# open2014.net
KiCad netlist of a schematic drawn in EAGLE
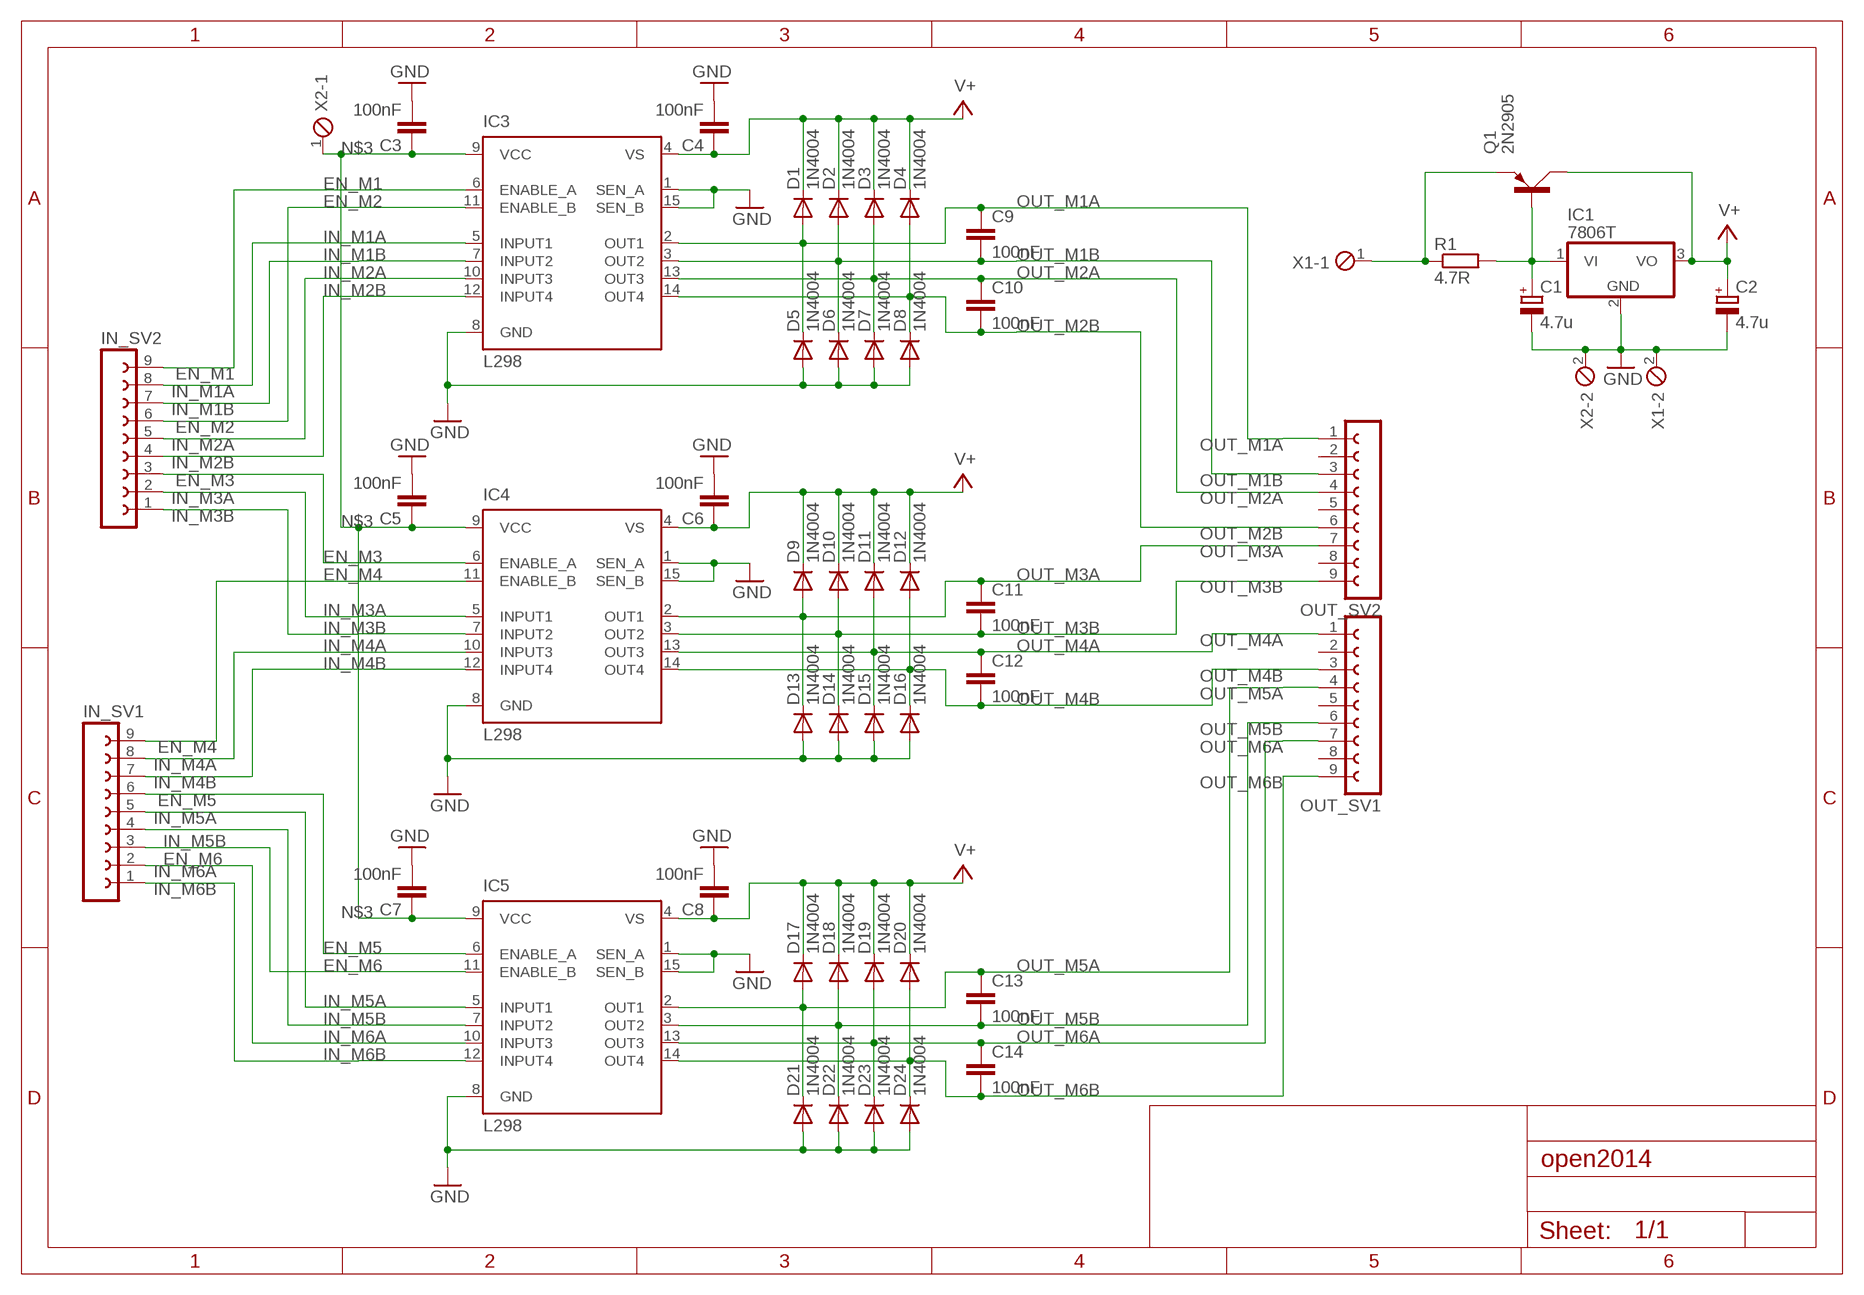
[diagram p0: schematic, sheet 1]

(export (version "E")
  (design (tool "Eeschema 10.0.6"))
  (components
    (comp (ref "C1")
      (value "4.7u")
      (footprint "eagle-import:E2,5-6")
      (libsource (lib "eagle-import") (part "CPOL-EUE2.5-6"))
    )
    (comp (ref "C2")
      (value "4.7u")
      (footprint "eagle-import:E2,5-6")
      (libsource (lib "eagle-import") (part "CPOL-EUE2.5-6"))
    )
    (comp (ref "C3")
      (value "100nF")
      (footprint "eagle-import:C050-050X075")
      (libsource (lib "eagle-import") (part "C-EU050-050X075"))
    )
    (comp (ref "C4")
      (value "100nF")
      (footprint "eagle-import:C050-050X075")
      (libsource (lib "eagle-import") (part "C-EU050-050X075"))
    )
    (comp (ref "C5")
      (value "100nF")
      (footprint "eagle-import:C050-050X075")
      (libsource (lib "eagle-import") (part "C-EU050-050X075"))
    )
    (comp (ref "C6")
      (value "100nF")
      (footprint "eagle-import:C050-050X075")
      (libsource (lib "eagle-import") (part "C-EU050-050X075"))
    )
    (comp (ref "C7")
      (value "100nF")
      (footprint "eagle-import:C050-050X075")
      (libsource (lib "eagle-import") (part "C-EU050-050X075"))
    )
    (comp (ref "C8")
      (value "100nF")
      (footprint "eagle-import:C050-050X075")
      (libsource (lib "eagle-import") (part "C-EU050-050X075"))
    )
    (comp (ref "C9")
      (value "100nF")
      (footprint "eagle-import:C050-050X075")
      (libsource (lib "eagle-import") (part "C-EU050-050X075"))
    )
    (comp (ref "C10")
      (value "100nF")
      (footprint "eagle-import:C050-050X075")
      (libsource (lib "eagle-import") (part "C-EU050-050X075"))
    )
    (comp (ref "C11")
      (value "100nF")
      (footprint "eagle-import:C050-050X075")
      (libsource (lib "eagle-import") (part "C-EU050-050X075"))
    )
    (comp (ref "C12")
      (value "100nF")
      (footprint "eagle-import:C050-050X075")
      (libsource (lib "eagle-import") (part "C-EU050-050X075"))
    )
    (comp (ref "C13")
      (value "100nF")
      (footprint "eagle-import:C050-050X075")
      (libsource (lib "eagle-import") (part "C-EU050-050X075"))
    )
    (comp (ref "C14")
      (value "100nF")
      (footprint "eagle-import:C050-050X075")
      (libsource (lib "eagle-import") (part "C-EU050-050X075"))
    )
    (comp (ref "D1")
      (value "1N4004")
      (footprint "eagle-import:DO41-10")
      (libsource (lib "eagle-import") (part "1N4004"))
    )
    (comp (ref "D2")
      (value "1N4004")
      (footprint "eagle-import:DO41-10")
      (libsource (lib "eagle-import") (part "1N4004"))
    )
    (comp (ref "D3")
      (value "1N4004")
      (footprint "eagle-import:DO41-10")
      (libsource (lib "eagle-import") (part "1N4004"))
    )
    (comp (ref "D4")
      (value "1N4004")
      (footprint "eagle-import:DO41-10")
      (libsource (lib "eagle-import") (part "1N4004"))
    )
    (comp (ref "D5")
      (value "1N4004")
      (footprint "eagle-import:DO41-10")
      (libsource (lib "eagle-import") (part "1N4004"))
    )
    (comp (ref "D6")
      (value "1N4004")
      (footprint "eagle-import:DO41-10")
      (libsource (lib "eagle-import") (part "1N4004"))
    )
    (comp (ref "D7")
      (value "1N4004")
      (footprint "eagle-import:DO41-10")
      (libsource (lib "eagle-import") (part "1N4004"))
    )
    (comp (ref "D8")
      (value "1N4004")
      (footprint "eagle-import:DO41-10")
      (libsource (lib "eagle-import") (part "1N4004"))
    )
    (comp (ref "D9")
      (value "1N4004")
      (footprint "eagle-import:DO41-10")
      (libsource (lib "eagle-import") (part "1N4004"))
    )
    (comp (ref "D10")
      (value "1N4004")
      (footprint "eagle-import:DO41-10")
      (libsource (lib "eagle-import") (part "1N4004"))
    )
    (comp (ref "D11")
      (value "1N4004")
      (footprint "eagle-import:DO41-10")
      (libsource (lib "eagle-import") (part "1N4004"))
    )
    (comp (ref "D12")
      (value "1N4004")
      (footprint "eagle-import:DO41-10")
      (libsource (lib "eagle-import") (part "1N4004"))
    )
    (comp (ref "D13")
      (value "1N4004")
      (footprint "eagle-import:DO41-10")
      (libsource (lib "eagle-import") (part "1N4004"))
    )
    (comp (ref "D14")
      (value "1N4004")
      (footprint "eagle-import:DO41-10")
      (libsource (lib "eagle-import") (part "1N4004"))
    )
    (comp (ref "D15")
      (value "1N4004")
      (footprint "eagle-import:DO41-10")
      (libsource (lib "eagle-import") (part "1N4004"))
    )
    (comp (ref "D16")
      (value "1N4004")
      (footprint "eagle-import:DO41-10")
      (libsource (lib "eagle-import") (part "1N4004"))
    )
    (comp (ref "D17")
      (value "1N4004")
      (footprint "eagle-import:DO41-10")
      (libsource (lib "eagle-import") (part "1N4004"))
    )
    (comp (ref "D18")
      (value "1N4004")
      (footprint "eagle-import:DO41-10")
      (libsource (lib "eagle-import") (part "1N4004"))
    )
    (comp (ref "D19")
      (value "1N4004")
      (footprint "eagle-import:DO41-10")
      (libsource (lib "eagle-import") (part "1N4004"))
    )
    (comp (ref "D20")
      (value "1N4004")
      (footprint "eagle-import:DO41-10")
      (libsource (lib "eagle-import") (part "1N4004"))
    )
    (comp (ref "D21")
      (value "1N4004")
      (footprint "eagle-import:DO41-10")
      (libsource (lib "eagle-import") (part "1N4004"))
    )
    (comp (ref "D22")
      (value "1N4004")
      (footprint "eagle-import:DO41-10")
      (libsource (lib "eagle-import") (part "1N4004"))
    )
    (comp (ref "D23")
      (value "1N4004")
      (footprint "eagle-import:DO41-10")
      (libsource (lib "eagle-import") (part "1N4004"))
    )
    (comp (ref "D24")
      (value "1N4004")
      (footprint "eagle-import:DO41-10")
      (libsource (lib "eagle-import") (part "1N4004"))
    )
    (comp (ref "IC1")
      (value "7806T")
      (footprint "eagle-import:TO220H")
      (libsource (lib "eagle-import") (part "78T06"))
    )
    (comp (ref "IC3")
      (value "L298")
      (footprint "eagle-import:MULTIWATT-15")
      (fields (field (name "MPN") "L298N"))
      (libsource (lib "eagle-import") (part "L298"))
    )
    (comp (ref "IC4")
      (value "L298")
      (footprint "eagle-import:MULTIWATT-15")
      (fields (field (name "MPN") "L298N"))
      (libsource (lib "eagle-import") (part "L298"))
    )
    (comp (ref "IC5")
      (value "L298")
      (footprint "eagle-import:MULTIWATT-15")
      (fields (field (name "MPN") "L298N"))
      (libsource (lib "eagle-import") (part "L298"))
    )
    (comp (ref "IN_SV1")
      (value "FE09-1")
      (footprint "eagle-import:FE09")
      (libsource (lib "eagle-import") (part "FE09-1"))
    )
    (comp (ref "IN_SV2")
      (value "FE09-1")
      (footprint "eagle-import:FE09")
      (libsource (lib "eagle-import") (part "FE09-1"))
    )
    (comp (ref "OUT_SV1")
      (value "FE09-1")
      (footprint "eagle-import:FE09")
      (libsource (lib "eagle-import") (part "FE09-1"))
    )
    (comp (ref "OUT_SV2")
      (value "FE09-1")
      (footprint "eagle-import:FE09")
      (libsource (lib "eagle-import") (part "FE09-1"))
    )
    (comp (ref "Q1")
      (value "2N2905")
      (footprint "eagle-import:TO39")
      (libsource (lib "eagle-import") (part "2N2905"))
    )
    (comp (ref "R1")
      (value "4.7R")
      (footprint "eagle-import:0411_15")
      (libsource (lib "eagle-import") (part "R-EU_0411/15"))
    )
    (comp (ref "X1")
      (value "MPT2")
      (footprint "eagle-import:2POL254")
      (libsource (lib "eagle-import") (part "MPT2"))
    )
    (comp (ref "X2")
      (value "MPT2")
      (footprint "eagle-import:2POL254")
      (libsource (lib "eagle-import") (part "MPT2"))
    )
  )
  (nets
    (net (code "1") (name "/EN_M1") (class "Default")
      (node (ref "IC3") (pin "6") (pinfunction "ENABLE_A_6") (pintype "input"))
      (node (ref "IN_SV2") (pin "9") (pinfunction "9_9") (pintype "passive"))
    )
    (net (code "2") (name "/EN_M2") (class "Default")
      (node (ref "IC3") (pin "11") (pinfunction "ENABLE_B_11") (pintype "input"))
      (node (ref "IN_SV2") (pin "6") (pinfunction "6_6") (pintype "passive"))
    )
    (net (code "3") (name "/EN_M3") (class "Default")
      (node (ref "IC4") (pin "6") (pinfunction "ENABLE_A_6") (pintype "input"))
      (node (ref "IN_SV2") (pin "3") (pinfunction "3_3") (pintype "passive"))
    )
    (net (code "4") (name "/EN_M4") (class "Default")
      (node (ref "IC4") (pin "11") (pinfunction "ENABLE_B_11") (pintype "input"))
      (node (ref "IN_SV1") (pin "9") (pinfunction "9_9") (pintype "passive"))
    )
    (net (code "5") (name "/EN_M5") (class "Default")
      (node (ref "IC5") (pin "6") (pinfunction "ENABLE_A_6") (pintype "input"))
      (node (ref "IN_SV1") (pin "6") (pinfunction "6_6") (pintype "passive"))
    )
    (net (code "6") (name "/EN_M6") (class "Default")
      (node (ref "IC5") (pin "11") (pinfunction "ENABLE_B_11") (pintype "input"))
      (node (ref "IN_SV1") (pin "3") (pinfunction "3_3") (pintype "passive"))
    )
    (net (code "7") (name "/IN_M1A") (class "Default")
      (node (ref "IC3") (pin "5") (pinfunction "INPUT1_5") (pintype "input"))
      (node (ref "IN_SV2") (pin "8") (pinfunction "8_8") (pintype "passive"))
    )
    (net (code "8") (name "/IN_M1B") (class "Default")
      (node (ref "IC3") (pin "7") (pinfunction "INPUT2_7") (pintype "input"))
      (node (ref "IN_SV2") (pin "7") (pinfunction "7_7") (pintype "passive"))
    )
    (net (code "9") (name "/IN_M2A") (class "Default")
      (node (ref "IC3") (pin "10") (pinfunction "INPUT3_10") (pintype "input"))
      (node (ref "IN_SV2") (pin "5") (pinfunction "5_5") (pintype "passive"))
    )
    (net (code "10") (name "/IN_M2B") (class "Default")
      (node (ref "IC3") (pin "12") (pinfunction "INPUT4_12") (pintype "input"))
      (node (ref "IN_SV2") (pin "4") (pinfunction "4_4") (pintype "passive"))
    )
    (net (code "11") (name "/IN_M3A") (class "Default")
      (node (ref "IC4") (pin "5") (pinfunction "INPUT1_5") (pintype "input"))
      (node (ref "IN_SV2") (pin "2") (pinfunction "2_2") (pintype "passive"))
    )
    (net (code "12") (name "/IN_M3B") (class "Default")
      (node (ref "IC4") (pin "7") (pinfunction "INPUT2_7") (pintype "input"))
      (node (ref "IN_SV2") (pin "1") (pinfunction "1_1") (pintype "passive"))
    )
    (net (code "13") (name "/IN_M4A") (class "Default")
      (node (ref "IC4") (pin "10") (pinfunction "INPUT3_10") (pintype "input"))
      (node (ref "IN_SV1") (pin "8") (pinfunction "8_8") (pintype "passive"))
    )
    (net (code "14") (name "/IN_M4B") (class "Default")
      (node (ref "IC4") (pin "12") (pinfunction "INPUT4_12") (pintype "input"))
      (node (ref "IN_SV1") (pin "7") (pinfunction "7_7") (pintype "passive"))
    )
    (net (code "15") (name "/IN_M5A") (class "Default")
      (node (ref "IC5") (pin "5") (pinfunction "INPUT1_5") (pintype "input"))
      (node (ref "IN_SV1") (pin "5") (pinfunction "5_5") (pintype "passive"))
    )
    (net (code "16") (name "/IN_M5B") (class "Default")
      (node (ref "IC5") (pin "7") (pinfunction "INPUT2_7") (pintype "input"))
      (node (ref "IN_SV1") (pin "4") (pinfunction "4_4") (pintype "passive"))
    )
    (net (code "17") (name "/IN_M6A") (class "Default")
      (node (ref "IC5") (pin "10") (pinfunction "INPUT3_10") (pintype "input"))
      (node (ref "IN_SV1") (pin "2") (pinfunction "2_2") (pintype "passive"))
    )
    (net (code "18") (name "/IN_M6B") (class "Default")
      (node (ref "IC5") (pin "12") (pinfunction "INPUT4_12") (pintype "input"))
      (node (ref "IN_SV1") (pin "1") (pinfunction "1_1") (pintype "passive"))
    )
    (net (code "19") (name "/N$3") (class "Default")
      (node (ref "C3") (pin "1") (pinfunction "1_1") (pintype "passive"))
      (node (ref "C5") (pin "1") (pinfunction "1_1") (pintype "passive"))
      (node (ref "C7") (pin "1") (pinfunction "1_1") (pintype "passive"))
      (node (ref "IC3") (pin "9") (pinfunction "VCC_9") (pintype "power_in"))
      (node (ref "IC4") (pin "9") (pinfunction "VCC_9") (pintype "power_in"))
      (node (ref "IC5") (pin "9") (pinfunction "VCC_9") (pintype "power_in"))
      (node (ref "X2") (pin "1") (pinfunction "1_1") (pintype "passive"))
    )
    (net (code "20") (name "/OUT_M1A") (class "Default")
      (node (ref "C9") (pin "1") (pinfunction "1_1") (pintype "passive"))
      (node (ref "D1") (pin "A") (pinfunction "A_A") (pintype "passive"))
      (node (ref "D5") (pin "C") (pinfunction "C_C") (pintype "passive"))
      (node (ref "IC3") (pin "2") (pinfunction "OUT1_2") (pintype "output"))
      (node (ref "OUT_SV2") (pin "1") (pinfunction "1_1") (pintype "passive"))
    )
    (net (code "21") (name "/OUT_M1B") (class "Default")
      (node (ref "C9") (pin "2") (pinfunction "2_2") (pintype "passive"))
      (node (ref "D2") (pin "A") (pinfunction "A_A") (pintype "passive"))
      (node (ref "D6") (pin "C") (pinfunction "C_C") (pintype "passive"))
      (node (ref "IC3") (pin "3") (pinfunction "OUT2_3") (pintype "output"))
      (node (ref "OUT_SV2") (pin "3") (pinfunction "3_3") (pintype "passive"))
    )
    (net (code "22") (name "/OUT_M2A") (class "Default")
      (node (ref "C10") (pin "1") (pinfunction "1_1") (pintype "passive"))
      (node (ref "D3") (pin "A") (pinfunction "A_A") (pintype "passive"))
      (node (ref "D7") (pin "C") (pinfunction "C_C") (pintype "passive"))
      (node (ref "IC3") (pin "13") (pinfunction "OUT3_13") (pintype "output"))
      (node (ref "OUT_SV2") (pin "4") (pinfunction "4_4") (pintype "passive"))
    )
    (net (code "23") (name "/OUT_M2B") (class "Default")
      (node (ref "C10") (pin "2") (pinfunction "2_2") (pintype "passive"))
      (node (ref "D4") (pin "A") (pinfunction "A_A") (pintype "passive"))
      (node (ref "D8") (pin "C") (pinfunction "C_C") (pintype "passive"))
      (node (ref "IC3") (pin "14") (pinfunction "OUT4_14") (pintype "output"))
      (node (ref "OUT_SV2") (pin "6") (pinfunction "6_6") (pintype "passive"))
    )
    (net (code "24") (name "/OUT_M3A") (class "Default")
      (node (ref "C11") (pin "1") (pinfunction "1_1") (pintype "passive"))
      (node (ref "D13") (pin "C") (pinfunction "C_C") (pintype "passive"))
      (node (ref "D9") (pin "A") (pinfunction "A_A") (pintype "passive"))
      (node (ref "IC4") (pin "2") (pinfunction "OUT1_2") (pintype "output"))
      (node (ref "OUT_SV2") (pin "7") (pinfunction "7_7") (pintype "passive"))
    )
    (net (code "25") (name "/OUT_M3B") (class "Default")
      (node (ref "C11") (pin "2") (pinfunction "2_2") (pintype "passive"))
      (node (ref "D10") (pin "A") (pinfunction "A_A") (pintype "passive"))
      (node (ref "D14") (pin "C") (pinfunction "C_C") (pintype "passive"))
      (node (ref "IC4") (pin "3") (pinfunction "OUT2_3") (pintype "output"))
      (node (ref "OUT_SV2") (pin "9") (pinfunction "9_9") (pintype "passive"))
    )
    (net (code "26") (name "/OUT_M4A") (class "Default")
      (node (ref "C12") (pin "1") (pinfunction "1_1") (pintype "passive"))
      (node (ref "D11") (pin "A") (pinfunction "A_A") (pintype "passive"))
      (node (ref "D15") (pin "C") (pinfunction "C_C") (pintype "passive"))
      (node (ref "IC4") (pin "13") (pinfunction "OUT3_13") (pintype "output"))
      (node (ref "OUT_SV1") (pin "1") (pinfunction "1_1") (pintype "passive"))
    )
    (net (code "27") (name "/OUT_M4B") (class "Default")
      (node (ref "C12") (pin "2") (pinfunction "2_2") (pintype "passive"))
      (node (ref "D12") (pin "A") (pinfunction "A_A") (pintype "passive"))
      (node (ref "D16") (pin "C") (pinfunction "C_C") (pintype "passive"))
      (node (ref "IC4") (pin "14") (pinfunction "OUT4_14") (pintype "output"))
      (node (ref "OUT_SV1") (pin "3") (pinfunction "3_3") (pintype "passive"))
    )
    (net (code "28") (name "/OUT_M5A") (class "Default")
      (node (ref "C13") (pin "1") (pinfunction "1_1") (pintype "passive"))
      (node (ref "D17") (pin "A") (pinfunction "A_A") (pintype "passive"))
      (node (ref "D21") (pin "C") (pinfunction "C_C") (pintype "passive"))
      (node (ref "IC5") (pin "2") (pinfunction "OUT1_2") (pintype "output"))
      (node (ref "OUT_SV1") (pin "4") (pinfunction "4_4") (pintype "passive"))
    )
    (net (code "29") (name "/OUT_M5B") (class "Default")
      (node (ref "C13") (pin "2") (pinfunction "2_2") (pintype "passive"))
      (node (ref "D18") (pin "A") (pinfunction "A_A") (pintype "passive"))
      (node (ref "D22") (pin "C") (pinfunction "C_C") (pintype "passive"))
      (node (ref "IC5") (pin "3") (pinfunction "OUT2_3") (pintype "output"))
      (node (ref "OUT_SV1") (pin "6") (pinfunction "6_6") (pintype "passive"))
    )
    (net (code "30") (name "/OUT_M6A") (class "Default")
      (node (ref "C14") (pin "1") (pinfunction "1_1") (pintype "passive"))
      (node (ref "D19") (pin "A") (pinfunction "A_A") (pintype "passive"))
      (node (ref "D23") (pin "C") (pinfunction "C_C") (pintype "passive"))
      (node (ref "IC5") (pin "13") (pinfunction "OUT3_13") (pintype "output"))
      (node (ref "OUT_SV1") (pin "7") (pinfunction "7_7") (pintype "passive"))
    )
    (net (code "31") (name "/OUT_M6B") (class "Default")
      (node (ref "C14") (pin "2") (pinfunction "2_2") (pintype "passive"))
      (node (ref "D20") (pin "A") (pinfunction "A_A") (pintype "passive"))
      (node (ref "D24") (pin "C") (pinfunction "C_C") (pintype "passive"))
      (node (ref "IC5") (pin "14") (pinfunction "OUT4_14") (pintype "output"))
      (node (ref "OUT_SV1") (pin "9") (pinfunction "9_9") (pintype "passive"))
    )
    (net (code "32") (name "GND") (class "Default")
      (node (ref "C1") (pin "-") (pinfunction "-_-") (pintype "passive"))
      (node (ref "C2") (pin "-") (pinfunction "-_-") (pintype "passive"))
      (node (ref "C3") (pin "2") (pinfunction "2_2") (pintype "passive"))
      (node (ref "C4") (pin "2") (pinfunction "2_2") (pintype "passive"))
      (node (ref "C5") (pin "2") (pinfunction "2_2") (pintype "passive"))
      (node (ref "C6") (pin "2") (pinfunction "2_2") (pintype "passive"))
      (node (ref "C7") (pin "2") (pinfunction "2_2") (pintype "passive"))
      (node (ref "C8") (pin "2") (pinfunction "2_2") (pintype "passive"))
      (node (ref "D13") (pin "A") (pinfunction "A_A") (pintype "passive"))
      (node (ref "D14") (pin "A") (pinfunction "A_A") (pintype "passive"))
      (node (ref "D15") (pin "A") (pinfunction "A_A") (pintype "passive"))
      (node (ref "D16") (pin "A") (pinfunction "A_A") (pintype "passive"))
      (node (ref "D21") (pin "A") (pinfunction "A_A") (pintype "passive"))
      (node (ref "D22") (pin "A") (pinfunction "A_A") (pintype "passive"))
      (node (ref "D23") (pin "A") (pinfunction "A_A") (pintype "passive"))
      (node (ref "D24") (pin "A") (pinfunction "A_A") (pintype "passive"))
      (node (ref "D5") (pin "A") (pinfunction "A_A") (pintype "passive"))
      (node (ref "D6") (pin "A") (pinfunction "A_A") (pintype "passive"))
      (node (ref "D7") (pin "A") (pinfunction "A_A") (pintype "passive"))
      (node (ref "D8") (pin "A") (pinfunction "A_A") (pintype "passive"))
      (node (ref "IC1") (pin "2") (pinfunction "GND_2") (pintype "passive"))
      (node (ref "IC3") (pin "1") (pinfunction "SEN_A_1") (pintype "input"))
      (node (ref "IC3") (pin "15") (pinfunction "SEN_B_15") (pintype "input"))
      (node (ref "IC3") (pin "8") (pinfunction "GND_8") (pintype "power_in"))
      (node (ref "IC4") (pin "1") (pinfunction "SEN_A_1") (pintype "input"))
      (node (ref "IC4") (pin "15") (pinfunction "SEN_B_15") (pintype "input"))
      (node (ref "IC4") (pin "8") (pinfunction "GND_8") (pintype "power_in"))
      (node (ref "IC5") (pin "1") (pinfunction "SEN_A_1") (pintype "input"))
      (node (ref "IC5") (pin "15") (pinfunction "SEN_B_15") (pintype "input"))
      (node (ref "IC5") (pin "8") (pinfunction "GND_8") (pintype "power_in"))
      (node (ref "X1") (pin "2") (pinfunction "1_2") (pintype "passive"))
      (node (ref "X2") (pin "2") (pinfunction "1_2") (pintype "passive"))
    )
    (net (code "33") (name "Net-(IC1-VI)") (class "Default")
      (node (ref "C1") (pin "+") (pinfunction "+_+") (pintype "passive"))
      (node (ref "IC1") (pin "1") (pinfunction "VI_1") (pintype "input"))
      (node (ref "Q1") (pin "2") (pinfunction "B_2") (pintype "passive"))
      (node (ref "R1") (pin "2") (pinfunction "2_2") (pintype "passive"))
    )
    (net (code "34") (name "Net-(Q1-E)") (class "Default")
      (node (ref "Q1") (pin "1") (pinfunction "E_1") (pintype "passive"))
      (node (ref "R1") (pin "1") (pinfunction "1_1") (pintype "passive"))
      (node (ref "X1") (pin "1") (pinfunction "1_1") (pintype "passive"))
    )
    (net (code "35") (name "V+") (class "Default")
      (node (ref "C2") (pin "+") (pinfunction "+_+") (pintype "passive"))
      (node (ref "C4") (pin "1") (pinfunction "1_1") (pintype "passive"))
      (node (ref "C6") (pin "1") (pinfunction "1_1") (pintype "passive"))
      (node (ref "C8") (pin "1") (pinfunction "1_1") (pintype "passive"))
      (node (ref "D1") (pin "C") (pinfunction "C_C") (pintype "passive"))
      (node (ref "D10") (pin "C") (pinfunction "C_C") (pintype "passive"))
      (node (ref "D11") (pin "C") (pinfunction "C_C") (pintype "passive"))
      (node (ref "D12") (pin "C") (pinfunction "C_C") (pintype "passive"))
      (node (ref "D17") (pin "C") (pinfunction "C_C") (pintype "passive"))
      (node (ref "D18") (pin "C") (pinfunction "C_C") (pintype "passive"))
      (node (ref "D19") (pin "C") (pinfunction "C_C") (pintype "passive"))
      (node (ref "D2") (pin "C") (pinfunction "C_C") (pintype "passive"))
      (node (ref "D20") (pin "C") (pinfunction "C_C") (pintype "passive"))
      (node (ref "D3") (pin "C") (pinfunction "C_C") (pintype "passive"))
      (node (ref "D4") (pin "C") (pinfunction "C_C") (pintype "passive"))
      (node (ref "D9") (pin "C") (pinfunction "C_C") (pintype "passive"))
      (node (ref "IC1") (pin "3") (pinfunction "VO_3") (pintype "passive"))
      (node (ref "IC3") (pin "4") (pinfunction "VS_4") (pintype "power_in"))
      (node (ref "IC4") (pin "4") (pinfunction "VS_4") (pintype "power_in"))
      (node (ref "IC5") (pin "4") (pinfunction "VS_4") (pintype "power_in"))
      (node (ref "Q1") (pin "3") (pinfunction "C_3") (pintype "passive"))
    )
    (net (code "36") (name "unconnected-(OUT_SV1-Pad2)") (class "Default")
      (node (ref "OUT_SV1") (pin "2") (pinfunction "2_2") (pintype "passive"))
    )
    (net (code "37") (name "unconnected-(OUT_SV1-Pad5)") (class "Default")
      (node (ref "OUT_SV1") (pin "5") (pinfunction "5_5") (pintype "passive"))
    )
    (net (code "38") (name "unconnected-(OUT_SV1-Pad8)") (class "Default")
      (node (ref "OUT_SV1") (pin "8") (pinfunction "8_8") (pintype "passive"))
    )
    (net (code "39") (name "unconnected-(OUT_SV2-Pad2)") (class "Default")
      (node (ref "OUT_SV2") (pin "2") (pinfunction "2_2") (pintype "passive"))
    )
    (net (code "40") (name "unconnected-(OUT_SV2-Pad5)") (class "Default")
      (node (ref "OUT_SV2") (pin "5") (pinfunction "5_5") (pintype "passive"))
    )
    (net (code "41") (name "unconnected-(OUT_SV2-Pad8)") (class "Default")
      (node (ref "OUT_SV2") (pin "8") (pinfunction "8_8") (pintype "passive"))
    )
  )
)
